# AutoIrrigator_Schematic.net
KiCad netlist of a schematic drawn in EAGLE
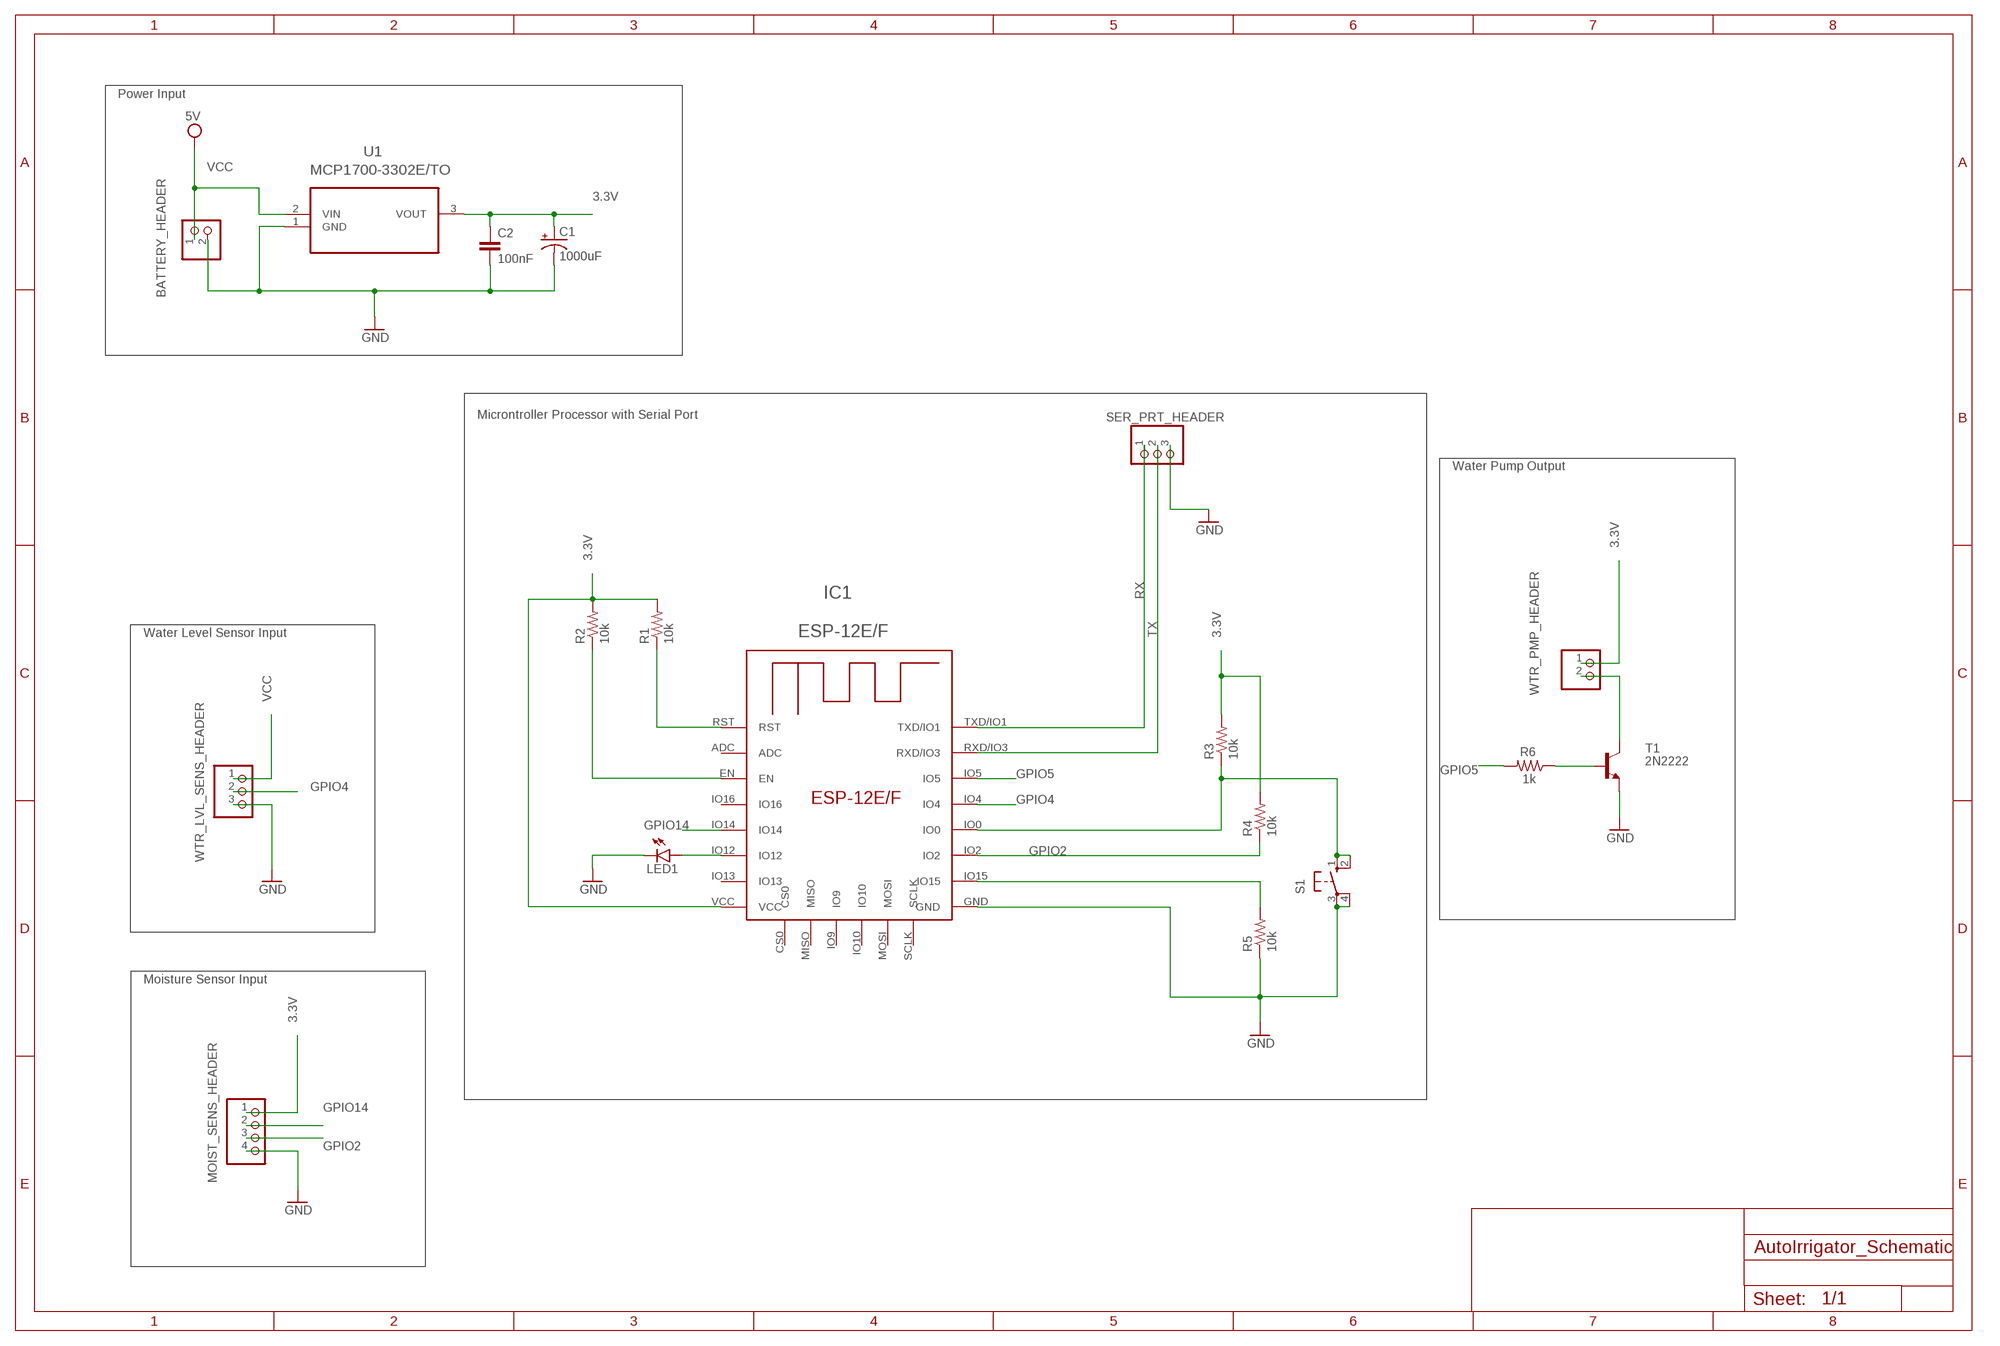
[diagram p0: schematic, sheet 1]

(export (version "E")
  (design (tool "Eeschema 10.0.6"))
  (components
    (comp (ref "BATTERY_HEADER")
      (value "PINHD-1X2")
      (footprint "eagle-import:1X02")
      (libsource (lib "eagle-import") (part "PINHD-1X2"))
    )
    (comp (ref "C1")
      (value "1000uF")
      (footprint "eagle-import:E2,5-6")
      (libsource (lib "eagle-import") (part "CPOL-USE2.5-6"))
    )
    (comp (ref "C2")
      (value "100nF")
      (footprint "eagle-import:C025-025X050")
      (libsource (lib "eagle-import") (part "C-EU025-025X050"))
    )
    (comp (ref "IC1")
      (value "ESP-12E/F")
      (footprint "eagle-import:ESP-12E")
      (libsource (lib "eagle-import") (part "ESP-12E/F"))
    )
    (comp (ref "LED1")
      (value "LED5MM")
      (footprint "eagle-import:LED5MM")
      (libsource (lib "eagle-import") (part "LED5MM"))
    )
    (comp (ref "MOIST_SENS_HEADER")
      (value "PINHD-1X4")
      (footprint "eagle-import:1X04")
      (libsource (lib "eagle-import") (part "PINHD-1X4"))
    )
    (comp (ref "R1")
      (value "10k")
      (footprint "eagle-import:0204_7")
      (libsource (lib "eagle-import") (part "R-US_0204/7"))
    )
    (comp (ref "R2")
      (value "10k")
      (footprint "eagle-import:0204_7")
      (libsource (lib "eagle-import") (part "R-US_0204/7"))
    )
    (comp (ref "R3")
      (value "10k")
      (footprint "eagle-import:0204_7")
      (libsource (lib "eagle-import") (part "R-US_0204/7"))
    )
    (comp (ref "R4")
      (value "10k")
      (footprint "eagle-import:0204_7")
      (libsource (lib "eagle-import") (part "R-US_0204/7"))
    )
    (comp (ref "R5")
      (value "10k")
      (footprint "eagle-import:0204_7")
      (libsource (lib "eagle-import") (part "R-US_0204/7"))
    )
    (comp (ref "R6")
      (value "1k")
      (footprint "eagle-import:0204_7")
      (libsource (lib "eagle-import") (part "R-US_0204/7"))
    )
    (comp (ref "S1")
      (value "10-XX")
      (footprint "eagle-import:B3F-10XX")
      (fields (field (name "MPN") "B3F-1000"))
      (libsource (lib "eagle-import") (part "10-XX"))
    )
    (comp (ref "SER_PRT_HEADER")
      (value "SER_PRT_HEADER")
      (footprint "eagle-import:1X03")
      (libsource (lib "eagle-import") (part "PINHD-1X3"))
    )
    (comp (ref "T1")
      (value "2N2222")
      (footprint "eagle-import:TO18")
      (libsource (lib "eagle-import") (part "2N2222"))
    )
    (comp (ref "U1")
      (value "MCP1700-3302E/TO")
      (footprint "eagle-import:TO127P254X495-3")
      (fields (field (name "MF") "Microchip"))
      (libsource (lib "eagle-import") (part "MCP1700-3302E/TO"))
    )
    (comp (ref "WTR_LVL_SENS_HEADER")
      (value "PINHD-1X3")
      (footprint "eagle-import:1X03")
      (libsource (lib "eagle-import") (part "PINHD-1X3"))
    )
    (comp (ref "WTR_PMP_HEADER")
      (value "PINHD-1X2")
      (footprint "eagle-import:1X02")
      (libsource (lib "eagle-import") (part "PINHD-1X2"))
    )
  )
  (nets
    (net (code "1") (name "/3.3V") (class "Default")
      (node (ref "C1") (pin "+") (pinfunction "+_+") (pintype "passive"))
      (node (ref "C2") (pin "1") (pinfunction "1_1") (pintype "passive"))
      (node (ref "IC1") (pin "VCC") (pinfunction "VCC_VCC") (pintype "power_in"))
      (node (ref "MOIST_SENS_HEADER") (pin "1") (pinfunction "1_1") (pintype "passive"))
      (node (ref "R1") (pin "2") (pinfunction "2_2") (pintype "passive"))
      (node (ref "R2") (pin "2") (pinfunction "2_2") (pintype "passive"))
      (node (ref "R3") (pin "2") (pinfunction "2_2") (pintype "passive"))
      (node (ref "R4") (pin "2") (pinfunction "2_2") (pintype "passive"))
      (node (ref "U1") (pin "3") (pinfunction "VOUT_3") (pintype "output"))
      (node (ref "WTR_PMP_HEADER") (pin "1") (pinfunction "1_1") (pintype "passive"))
    )
    (net (code "2") (name "/GPIO2") (class "Default")
      (node (ref "IC1") (pin "IO2") (pinfunction "IO2_IO2") (pintype "bidirectional"))
      (node (ref "MOIST_SENS_HEADER") (pin "3") (pinfunction "3_3") (pintype "passive"))
      (node (ref "R4") (pin "1") (pinfunction "1_1") (pintype "passive"))
    )
    (net (code "3") (name "/GPIO4") (class "Default")
      (node (ref "IC1") (pin "IO4") (pinfunction "IO4_IO4") (pintype "bidirectional"))
      (node (ref "WTR_LVL_SENS_HEADER") (pin "2") (pinfunction "2_2") (pintype "passive"))
    )
    (net (code "4") (name "/GPIO5") (class "Default")
      (node (ref "IC1") (pin "IO5") (pinfunction "IO5_IO5") (pintype "bidirectional"))
      (node (ref "R6") (pin "2") (pinfunction "2_2") (pintype "passive"))
    )
    (net (code "5") (name "/GPIO14") (class "Default")
      (node (ref "IC1") (pin "IO14") (pinfunction "IO14_IO14") (pintype "bidirectional"))
      (node (ref "MOIST_SENS_HEADER") (pin "2") (pinfunction "2_2") (pintype "passive"))
    )
    (net (code "6") (name "/RX") (class "Default")
      (node (ref "IC1") (pin "TXD/IO1") (pinfunction "TXD/IO1_TXD/IO1") (pintype "bidirectional"))
      (node (ref "SER_PRT_HEADER") (pin "1") (pinfunction "1_1") (pintype "passive"))
    )
    (net (code "7") (name "/TX") (class "Default")
      (node (ref "IC1") (pin "RXD/IO3") (pinfunction "RXD/IO3_RXD/IO3") (pintype "bidirectional"))
      (node (ref "SER_PRT_HEADER") (pin "2") (pinfunction "2_2") (pintype "passive"))
    )
    (net (code "8") (name "5V") (class "Default")
      (node (ref "BATTERY_HEADER") (pin "1") (pinfunction "1_1") (pintype "passive"))
      (node (ref "U1") (pin "2") (pinfunction "VIN_2") (pintype "input"))
      (node (ref "WTR_LVL_SENS_HEADER") (pin "1") (pinfunction "1_1") (pintype "passive"))
    )
    (net (code "9") (name "GND") (class "Default")
      (node (ref "BATTERY_HEADER") (pin "2") (pinfunction "2_2") (pintype "passive"))
      (node (ref "C1") (pin "-") (pinfunction "-_-") (pintype "passive"))
      (node (ref "C2") (pin "2") (pinfunction "2_2") (pintype "passive"))
      (node (ref "IC1") (pin "GND") (pinfunction "GND_GND") (pintype "power_in"))
      (node (ref "LED1") (pin "K") (pinfunction "C_K") (pintype "passive"))
      (node (ref "MOIST_SENS_HEADER") (pin "4") (pinfunction "4_4") (pintype "passive"))
      (node (ref "R5") (pin "1") (pinfunction "1_1") (pintype "passive"))
      (node (ref "S1") (pin "3") (pinfunction "P_3") (pintype "passive"))
      (node (ref "S1") (pin "4") (pinfunction "P1_4") (pintype "passive"))
      (node (ref "SER_PRT_HEADER") (pin "3") (pinfunction "3_3") (pintype "passive"))
      (node (ref "T1") (pin "1") (pinfunction "E_1") (pintype "passive"))
      (node (ref "U1") (pin "1") (pinfunction "GND_1") (pintype "passive"))
      (node (ref "WTR_LVL_SENS_HEADER") (pin "3") (pinfunction "3_3") (pintype "passive"))
    )
    (net (code "10") (name "Net-(IC1-PadEN)") (class "Default")
      (node (ref "IC1") (pin "EN") (pinfunction "EN_EN") (pintype "bidirectional"))
      (node (ref "R2") (pin "1") (pinfunction "1_1") (pintype "passive"))
    )
    (net (code "11") (name "Net-(IC1-PadIO12)") (class "Default")
      (node (ref "IC1") (pin "IO12") (pinfunction "IO12_IO12") (pintype "bidirectional"))
      (node (ref "LED1") (pin "A") (pinfunction "A_A") (pintype "passive"))
    )
    (net (code "12") (name "Net-(IC1-PadIO15)") (class "Default")
      (node (ref "IC1") (pin "IO15") (pinfunction "IO15_IO15") (pintype "bidirectional"))
      (node (ref "R5") (pin "2") (pinfunction "2_2") (pintype "passive"))
    )
    (net (code "13") (name "Net-(IC1-PadRST)") (class "Default")
      (node (ref "IC1") (pin "RST") (pinfunction "RST_RST") (pintype "input"))
      (node (ref "R1") (pin "1") (pinfunction "1_1") (pintype "passive"))
    )
    (net (code "14") (name "Net-(S1-S)") (class "Default")
      (node (ref "IC1") (pin "IO0") (pinfunction "IO0_IO0") (pintype "bidirectional"))
      (node (ref "R3") (pin "1") (pinfunction "1_1") (pintype "passive"))
      (node (ref "S1") (pin "1") (pinfunction "S_1") (pintype "passive"))
      (node (ref "S1") (pin "2") (pinfunction "S1_2") (pintype "passive"))
    )
    (net (code "15") (name "Net-(T1-B)") (class "Default")
      (node (ref "R6") (pin "1") (pinfunction "1_1") (pintype "passive"))
      (node (ref "T1") (pin "2") (pinfunction "B_2") (pintype "passive"))
    )
    (net (code "16") (name "Net-(T1-C)") (class "Default")
      (node (ref "T1") (pin "3") (pinfunction "C_3") (pintype "passive"))
      (node (ref "WTR_PMP_HEADER") (pin "2") (pinfunction "2_2") (pintype "passive"))
    )
    (net (code "17") (name "unconnected-(IC1-PadADC)") (class "Default")
      (node (ref "IC1") (pin "ADC") (pinfunction "ADC_ADC") (pintype "bidirectional"))
    )
    (net (code "18") (name "unconnected-(IC1-PadCS0)") (class "Default")
      (node (ref "IC1") (pin "CS0") (pinfunction "CS0_CS0") (pintype "bidirectional"))
    )
    (net (code "19") (name "unconnected-(IC1-PadIO9)") (class "Default")
      (node (ref "IC1") (pin "IO9") (pinfunction "IO9_IO9") (pintype "bidirectional"))
    )
    (net (code "20") (name "unconnected-(IC1-PadIO10)") (class "Default")
      (node (ref "IC1") (pin "IO10") (pinfunction "IO10_IO10") (pintype "bidirectional"))
    )
    (net (code "21") (name "unconnected-(IC1-PadIO13)") (class "Default")
      (node (ref "IC1") (pin "IO13") (pinfunction "IO13_IO13") (pintype "bidirectional"))
    )
    (net (code "22") (name "unconnected-(IC1-PadIO16)") (class "Default")
      (node (ref "IC1") (pin "IO16") (pinfunction "IO16_IO16") (pintype "bidirectional"))
    )
    (net (code "23") (name "unconnected-(IC1-PadMISO)") (class "Default")
      (node (ref "IC1") (pin "MISO") (pinfunction "MISO_MISO") (pintype "bidirectional"))
    )
    (net (code "24") (name "unconnected-(IC1-PadMOSI)") (class "Default")
      (node (ref "IC1") (pin "MOSI") (pinfunction "MOSI_MOSI") (pintype "bidirectional"))
    )
    (net (code "25") (name "unconnected-(IC1-PadSCLK)") (class "Default")
      (node (ref "IC1") (pin "SCLK") (pinfunction "SCLK_SCLK") (pintype "bidirectional"))
    )
  )
)
